# CAN.net
KiCad netlist of a schematic drawn in Altium Designer
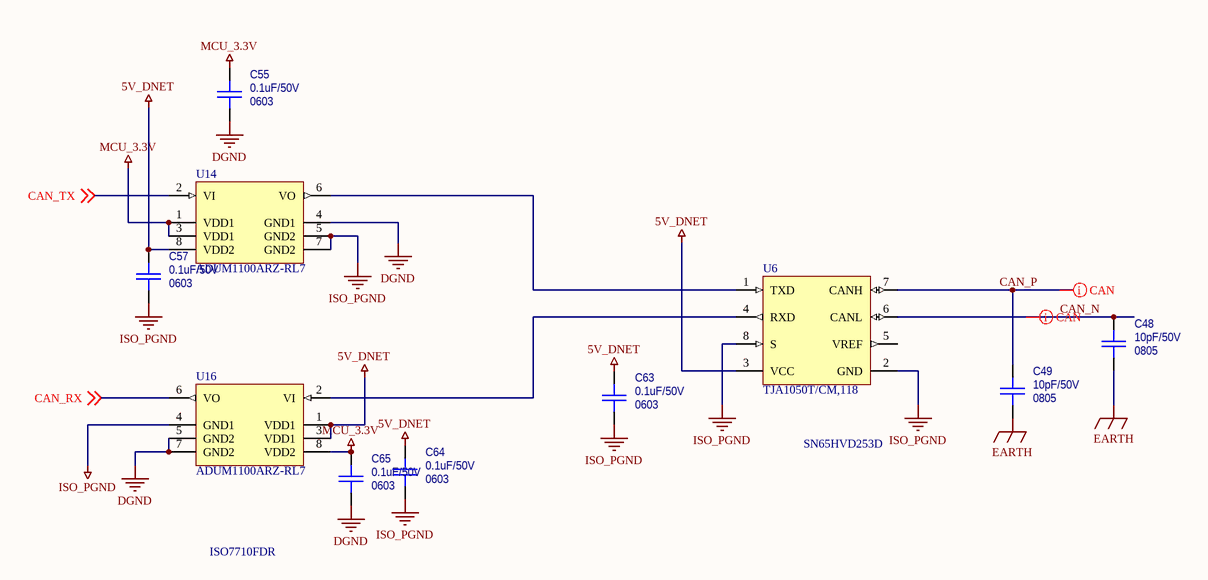
[diagram p0: CAN.SchDoc]

(export (version "E")
  (design (tool "Eeschema 10.0.6"))
  (components
    (comp (ref "C48")
      (value "10pF/50V")
      (footprint "CAPC2012X127N_0805")
      (fields (field (name "TOLERANCE") "[tol]") (field (name "PACKAGE") "0805"))
      (libsource (lib "Karl") (part "Capacitor_0805"))
    )
    (comp (ref "C49")
      (value "10pF/50V")
      (footprint "CAPC2012X127N_0805")
      (fields (field (name "TOLERANCE") "[tol]") (field (name "PACKAGE") "0805"))
      (libsource (lib "Karl") (part "Capacitor_0805"))
    )
    (comp (ref "C55")
      (value "0.1uF/50V")
      (footprint "CAPC1608X092N_0603")
      (fields
        (field (name "PARTNUMBER") "CC0603KRX7R9BB104")
        (field (name "TOLERANCE") "[tol]")
        (field (name "PACKAGE") "0603")
      )
      (libsource (lib "Karl") (part "Capacitor_0603"))
    )
    (comp (ref "C57")
      (value "0.1uF/50V")
      (footprint "CAPC1608X092N_0603")
      (fields
        (field (name "PARTNUMBER") "CC0603KRX7R9BB104")
        (field (name "TOLERANCE") "[tol]")
        (field (name "PACKAGE") "0603")
      )
      (libsource (lib "Karl") (part "Capacitor_0603"))
    )
    (comp (ref "C63")
      (value "0.1uF/50V")
      (footprint "CAPC1608X092N_0603")
      (fields
        (field (name "PARTNUMBER") "CC0603KRX7R9BB104")
        (field (name "TOLERANCE") "[tol]")
        (field (name "PACKAGE") "0603")
      )
      (libsource (lib "Karl") (part "Capacitor_0603"))
    )
    (comp (ref "C64")
      (value "0.1uF/50V")
      (footprint "CAPC1608X092N_0603")
      (fields
        (field (name "PARTNUMBER") "CC0603KRX7R9BB104")
        (field (name "TOLERANCE") "[tol]")
        (field (name "PACKAGE") "0603")
      )
      (libsource (lib "Karl") (part "Capacitor_0603"))
    )
    (comp (ref "C65")
      (value "0.1uF/50V")
      (footprint "CAPC1608X092N_0603")
      (fields
        (field (name "PARTNUMBER") "CC0603KRX7R9BB104")
        (field (name "TOLERANCE") "[tol]")
        (field (name "PACKAGE") "0603")
      )
      (libsource (lib "Karl") (part "Capacitor_0603"))
    )
    (comp (ref "U6")
      (value "TJA1050T/CM,118")
      (footprint "NXP-SOT96-1_N")
      (libsource (lib "Bogen") (part "TJA1050T/CM,118"))
    )
    (comp (ref "U14")
      (value "ADUM1100ARZ-RL7")
      (footprint "ADI-R-8_N")
      (libsource (lib "Bogen") (part "ADUM1100ARZ-RL7"))
    )
    (comp (ref "U16")
      (value "ADUM1100ARZ-RL7")
      (footprint "ADI-R-8_N")
      (libsource (lib "") (part "ADUM1100ARZ-RL7_1"))
    )
  )
  (nets
    (net (code "1") (name "/CAN_N") (class "Default")
      (node (ref "C48") (pin "1") (pinfunction "1_1") (pintype "passive"))
      (node (ref "U6") (pin "6") (pinfunction "CANL_6") (pintype "bidirectional"))
    )
    (net (code "2") (name "/CAN_P") (class "Default")
      (node (ref "C49") (pin "1") (pinfunction "1_1") (pintype "passive"))
      (node (ref "U6") (pin "7") (pinfunction "CANH_7") (pintype "bidirectional"))
    )
    (net (code "3") (name "5V_DNET") (class "Default")
      (node (ref "C57") (pin "1") (pinfunction "1_1") (pintype "passive"))
      (node (ref "C63") (pin "1") (pinfunction "1_1") (pintype "passive"))
      (node (ref "C64") (pin "1") (pinfunction "1_1") (pintype "passive"))
      (node (ref "U14") (pin "8") (pinfunction "VDD2_8") (pintype "power_in"))
      (node (ref "U16") (pin "1") (pinfunction "VDD1_1") (pintype "power_in"))
      (node (ref "U16") (pin "3") (pinfunction "VDD1_3") (pintype "power_in"))
      (node (ref "U6") (pin "3") (pinfunction "VCC_3") (pintype "power_in"))
    )
    (net (code "4") (name "CAN_RX") (class "Default")
      (node (ref "U16") (pin "6") (pinfunction "VO_6") (pintype "output"))
    )
    (net (code "5") (name "CAN_TX") (class "Default")
      (node (ref "U14") (pin "2") (pinfunction "VI_2") (pintype "input"))
    )
    (net (code "6") (name "DGND") (class "Default")
      (node (ref "C55") (pin "2") (pinfunction "2_2") (pintype "passive"))
      (node (ref "C65") (pin "2") (pinfunction "2_2") (pintype "passive"))
      (node (ref "U14") (pin "4") (pinfunction "GND1_4") (pintype "power_in"))
      (node (ref "U16") (pin "5") (pinfunction "GND2_5") (pintype "power_in"))
      (node (ref "U16") (pin "7") (pinfunction "GND2_7") (pintype "power_in"))
    )
    (net (code "7") (name "EARTH") (class "Default")
      (node (ref "C48") (pin "2") (pinfunction "2_2") (pintype "passive"))
      (node (ref "C49") (pin "2") (pinfunction "2_2") (pintype "passive"))
    )
    (net (code "8") (name "ISO_PGND") (class "Default")
      (node (ref "C57") (pin "2") (pinfunction "2_2") (pintype "passive"))
      (node (ref "C63") (pin "2") (pinfunction "2_2") (pintype "passive"))
      (node (ref "C64") (pin "2") (pinfunction "2_2") (pintype "passive"))
      (node (ref "U14") (pin "5") (pinfunction "GND2_5") (pintype "power_in"))
      (node (ref "U14") (pin "7") (pinfunction "GND2_7") (pintype "power_in"))
      (node (ref "U16") (pin "4") (pinfunction "GND1_4") (pintype "power_in"))
      (node (ref "U6") (pin "2") (pinfunction "GND_2") (pintype "power_in"))
      (node (ref "U6") (pin "8") (pinfunction "S_8") (pintype "input"))
    )
    (net (code "9") (name "MCU_3.3V") (class "Default")
      (node (ref "C55") (pin "1") (pinfunction "1_1") (pintype "passive"))
      (node (ref "C65") (pin "1") (pinfunction "1_1") (pintype "passive"))
      (node (ref "U14") (pin "1") (pinfunction "VDD1_1") (pintype "power_in"))
      (node (ref "U14") (pin "3") (pinfunction "VDD1_3") (pintype "power_in"))
      (node (ref "U16") (pin "8") (pinfunction "VDD2_8") (pintype "power_in"))
    )
    (net (code "10") (name "Net-(U14-VO)") (class "Default")
      (node (ref "U14") (pin "6") (pinfunction "VO_6") (pintype "output"))
      (node (ref "U6") (pin "1") (pinfunction "TXD_1") (pintype "input"))
    )
    (net (code "11") (name "Net-(U16-VI)") (class "Default")
      (node (ref "U16") (pin "2") (pinfunction "VI_2") (pintype "input"))
      (node (ref "U6") (pin "4") (pinfunction "RXD_4") (pintype "output"))
    )
    (net (code "12") (name "unconnected-(U6-VREF-Pad5)") (class "Default")
      (node (ref "U6") (pin "5") (pinfunction "VREF_5") (pintype "output"))
    )
  )
)
